# pcan-001.net
KiCad netlist of a schematic drawn in EAGLE
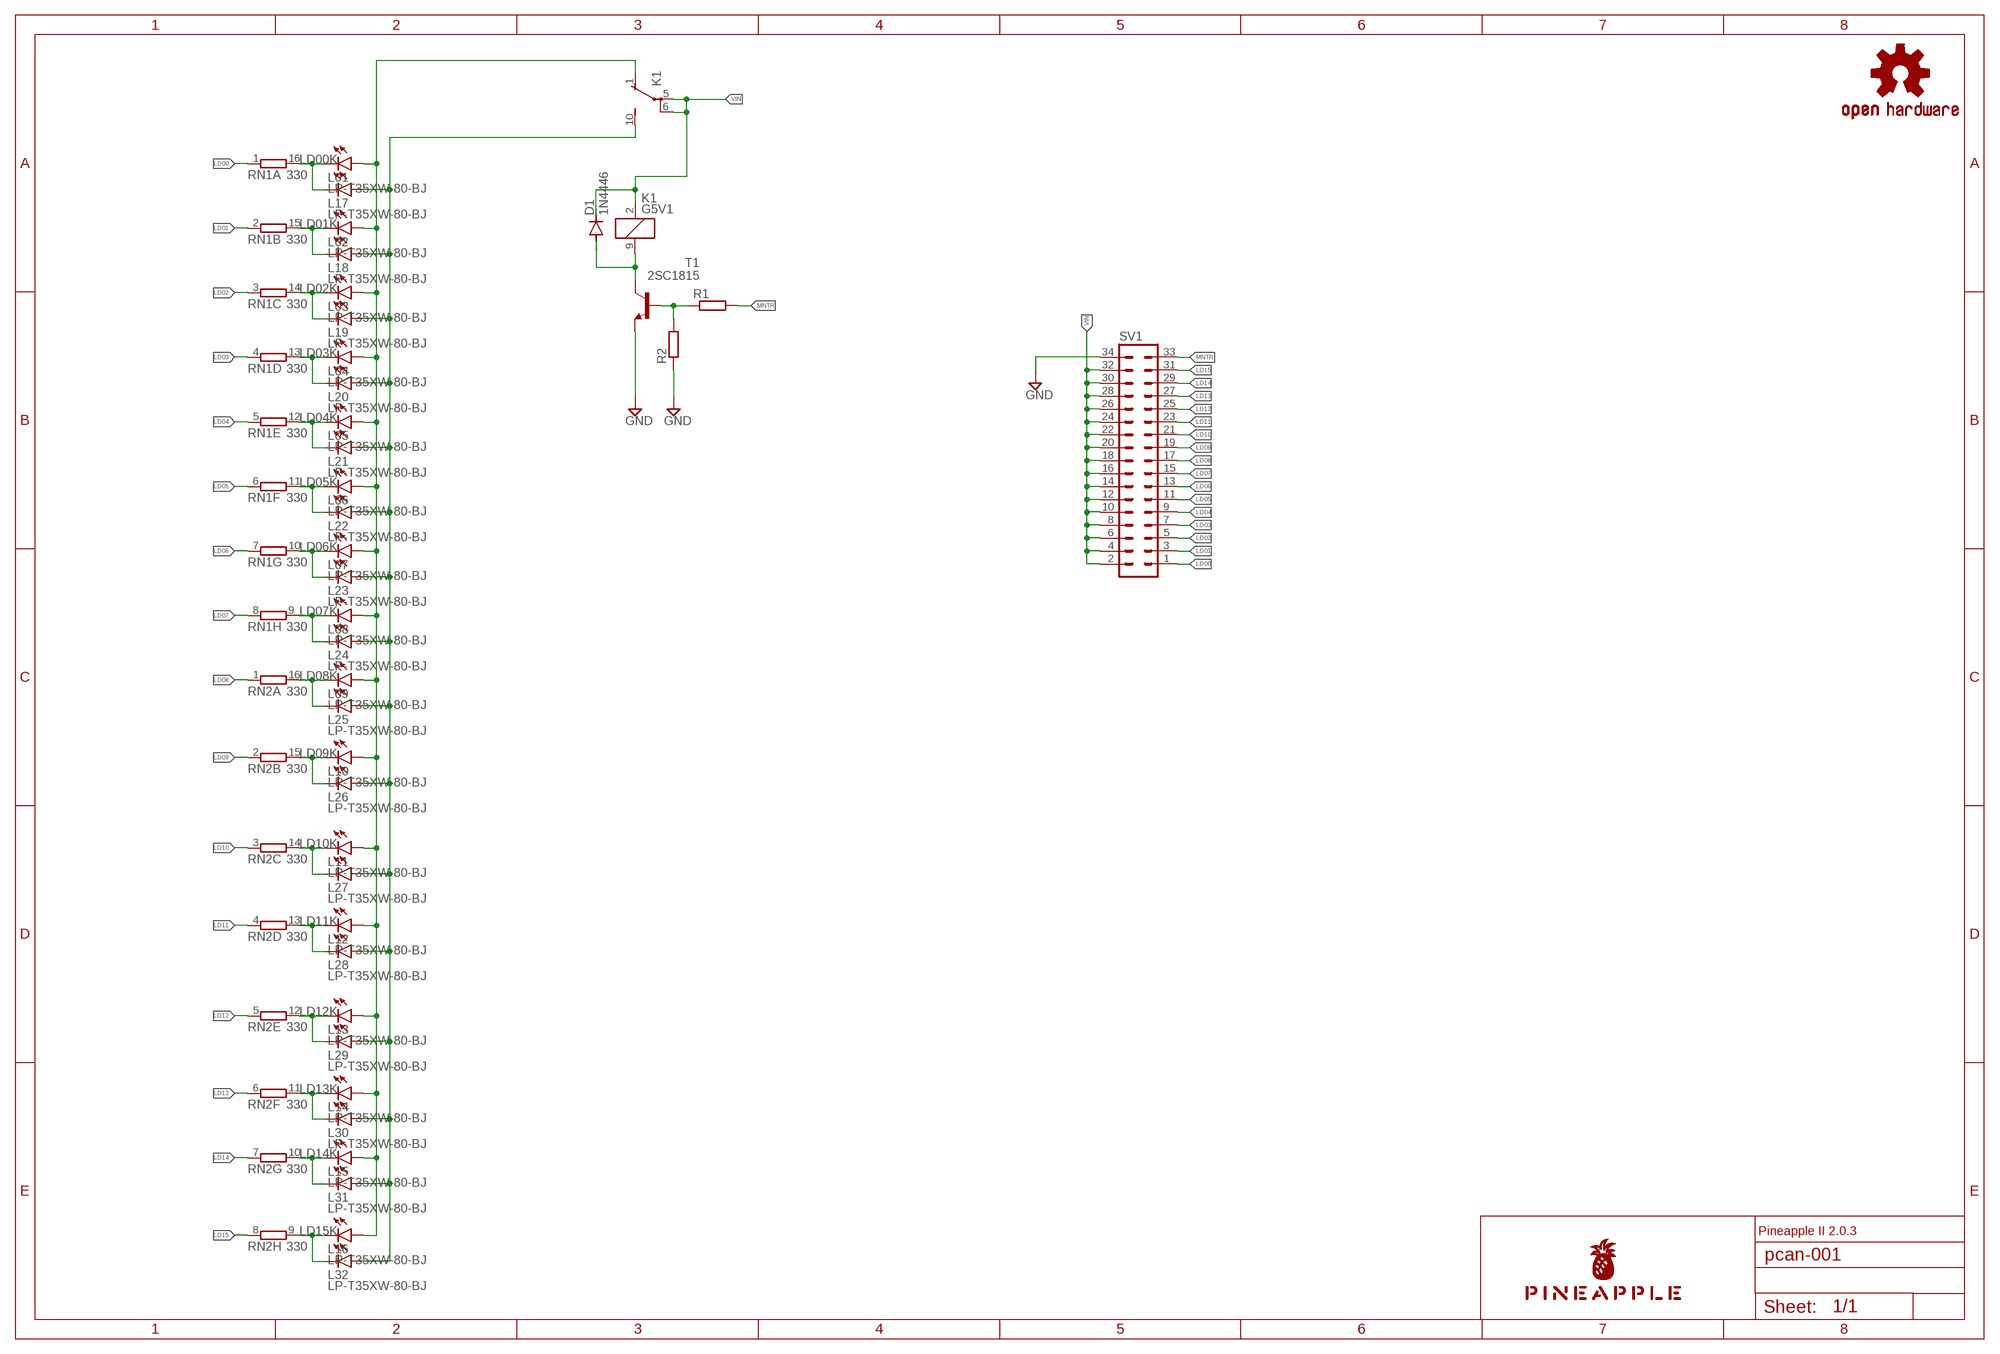
[diagram p0: schematic, sheet 1]

(export (version "E")
  (design (tool "Eeschema 10.0.6"))
  (components
    (comp (ref "D1")
      (value "1N4446")
      (footprint "eagle-import:DO35-10")
      (libsource (lib "eagle-import") (part "1N4446"))
    )
    (comp (ref "K1")
      (value "G5V1")
      (footprint "eagle-import:G5V1")
      (fields (field (name "MPN") "G5V-1-DC24"))
      (libsource (lib "eagle-import") (part "G5V1"))
    )
    (comp (ref "L01")
      (value "LP-T35XW-80-BJ")
      (footprint "eagle-import:KA-3528ASYC")
      (libsource (lib "eagle-import") (part "LEDKA-3528ASYC"))
    )
    (comp (ref "L02")
      (value "LP-T35XW-80-BJ")
      (footprint "eagle-import:KA-3528ASYC")
      (libsource (lib "eagle-import") (part "LEDKA-3528ASYC"))
    )
    (comp (ref "L03")
      (value "LP-T35XW-80-BJ")
      (footprint "eagle-import:KA-3528ASYC")
      (libsource (lib "eagle-import") (part "LEDKA-3528ASYC"))
    )
    (comp (ref "L04")
      (value "LP-T35XW-80-BJ")
      (footprint "eagle-import:KA-3528ASYC")
      (libsource (lib "eagle-import") (part "LEDKA-3528ASYC"))
    )
    (comp (ref "L05")
      (value "LP-T35XW-80-BJ")
      (footprint "eagle-import:KA-3528ASYC")
      (libsource (lib "eagle-import") (part "LEDKA-3528ASYC"))
    )
    (comp (ref "L06")
      (value "LP-T35XW-80-BJ")
      (footprint "eagle-import:KA-3528ASYC")
      (libsource (lib "eagle-import") (part "LEDKA-3528ASYC"))
    )
    (comp (ref "L07")
      (value "LP-T35XW-80-BJ")
      (footprint "eagle-import:KA-3528ASYC")
      (libsource (lib "eagle-import") (part "LEDKA-3528ASYC"))
    )
    (comp (ref "L08")
      (value "LP-T35XW-80-BJ")
      (footprint "eagle-import:KA-3528ASYC")
      (libsource (lib "eagle-import") (part "LEDKA-3528ASYC"))
    )
    (comp (ref "L09")
      (value "LP-T35XW-80-BJ")
      (footprint "eagle-import:KA-3528ASYC")
      (libsource (lib "eagle-import") (part "LEDKA-3528ASYC"))
    )
    (comp (ref "L10")
      (value "LP-T35XW-80-BJ")
      (footprint "eagle-import:KA-3528ASYC")
      (libsource (lib "eagle-import") (part "LEDKA-3528ASYC"))
    )
    (comp (ref "L11")
      (value "LP-T35XW-80-BJ")
      (footprint "eagle-import:KA-3528ASYC")
      (libsource (lib "eagle-import") (part "LEDKA-3528ASYC"))
    )
    (comp (ref "L12")
      (value "LP-T35XW-80-BJ")
      (footprint "eagle-import:KA-3528ASYC")
      (libsource (lib "eagle-import") (part "LEDKA-3528ASYC"))
    )
    (comp (ref "L13")
      (value "LP-T35XW-80-BJ")
      (footprint "eagle-import:KA-3528ASYC")
      (libsource (lib "eagle-import") (part "LEDKA-3528ASYC"))
    )
    (comp (ref "L14")
      (value "LP-T35XW-80-BJ")
      (footprint "eagle-import:KA-3528ASYC")
      (libsource (lib "eagle-import") (part "LEDKA-3528ASYC"))
    )
    (comp (ref "L15")
      (value "LP-T35XW-80-BJ")
      (footprint "eagle-import:KA-3528ASYC")
      (libsource (lib "eagle-import") (part "LEDKA-3528ASYC"))
    )
    (comp (ref "L16")
      (value "LP-T35XW-80-BJ")
      (footprint "eagle-import:KA-3528ASYC")
      (libsource (lib "eagle-import") (part "LEDKA-3528ASYC"))
    )
    (comp (ref "L17")
      (value "LP-T35XW-80-BJ")
      (footprint "eagle-import:KA-3528ASYC")
      (libsource (lib "eagle-import") (part "LEDKA-3528ASYC"))
    )
    (comp (ref "L18")
      (value "LP-T35XW-80-BJ")
      (footprint "eagle-import:KA-3528ASYC")
      (libsource (lib "eagle-import") (part "LEDKA-3528ASYC"))
    )
    (comp (ref "L19")
      (value "LP-T35XW-80-BJ")
      (footprint "eagle-import:KA-3528ASYC")
      (libsource (lib "eagle-import") (part "LEDKA-3528ASYC"))
    )
    (comp (ref "L20")
      (value "LP-T35XW-80-BJ")
      (footprint "eagle-import:KA-3528ASYC")
      (libsource (lib "eagle-import") (part "LEDKA-3528ASYC"))
    )
    (comp (ref "L21")
      (value "LP-T35XW-80-BJ")
      (footprint "eagle-import:KA-3528ASYC")
      (libsource (lib "eagle-import") (part "LEDKA-3528ASYC"))
    )
    (comp (ref "L22")
      (value "LP-T35XW-80-BJ")
      (footprint "eagle-import:KA-3528ASYC")
      (libsource (lib "eagle-import") (part "LEDKA-3528ASYC"))
    )
    (comp (ref "L23")
      (value "LP-T35XW-80-BJ")
      (footprint "eagle-import:KA-3528ASYC")
      (libsource (lib "eagle-import") (part "LEDKA-3528ASYC"))
    )
    (comp (ref "L24")
      (value "LP-T35XW-80-BJ")
      (footprint "eagle-import:KA-3528ASYC")
      (libsource (lib "eagle-import") (part "LEDKA-3528ASYC"))
    )
    (comp (ref "L25")
      (value "LP-T35XW-80-BJ")
      (footprint "eagle-import:KA-3528ASYC")
      (libsource (lib "eagle-import") (part "LEDKA-3528ASYC"))
    )
    (comp (ref "L26")
      (value "LP-T35XW-80-BJ")
      (footprint "eagle-import:KA-3528ASYC")
      (libsource (lib "eagle-import") (part "LEDKA-3528ASYC"))
    )
    (comp (ref "L27")
      (value "LP-T35XW-80-BJ")
      (footprint "eagle-import:KA-3528ASYC")
      (libsource (lib "eagle-import") (part "LEDKA-3528ASYC"))
    )
    (comp (ref "L28")
      (value "LP-T35XW-80-BJ")
      (footprint "eagle-import:KA-3528ASYC")
      (libsource (lib "eagle-import") (part "LEDKA-3528ASYC"))
    )
    (comp (ref "L29")
      (value "LP-T35XW-80-BJ")
      (footprint "eagle-import:KA-3528ASYC")
      (libsource (lib "eagle-import") (part "LEDKA-3528ASYC"))
    )
    (comp (ref "L30")
      (value "LP-T35XW-80-BJ")
      (footprint "eagle-import:KA-3528ASYC")
      (libsource (lib "eagle-import") (part "LEDKA-3528ASYC"))
    )
    (comp (ref "L31")
      (value "LP-T35XW-80-BJ")
      (footprint "eagle-import:KA-3528ASYC")
      (libsource (lib "eagle-import") (part "LEDKA-3528ASYC"))
    )
    (comp (ref "L32")
      (value "LP-T35XW-80-BJ")
      (footprint "eagle-import:KA-3528ASYC")
      (libsource (lib "eagle-import") (part "LEDKA-3528ASYC"))
    )
    (comp (ref "LOGO1")
      (value "OSHW-LOGOS-COPPER")
      (footprint "eagle-import:OSHW-LOGO-S_COPPER")
      (libsource (lib "eagle-import") (part "OSHW-LOGOS-COPPER"))
    )
    (comp (ref "R1")
      (value "R-EU_0204/5")
      (footprint "eagle-import:0204_5")
      (libsource (lib "eagle-import") (part "R-EU_0204/5"))
    )
    (comp (ref "R2")
      (value "R-EU_0204/5")
      (footprint "eagle-import:0204_5")
      (libsource (lib "eagle-import") (part "R-EU_0204/5"))
    )
    (comp (ref "RN1")
      (value "330")
      (footprint "eagle-import:DIL16")
      (libsource (lib "eagle-import") (part "8R-N"))
    )
    (comp (ref "RN2")
      (value "330")
      (footprint "eagle-import:DIL16")
      (libsource (lib "eagle-import") (part "8R-N"))
    )
    (comp (ref "SV1")
      (value "ML34L")
      (footprint "eagle-import:ML34L")
      (libsource (lib "eagle-import") (part "ML34L"))
    )
    (comp (ref "T1")
      (value "2SC1815")
      (footprint "eagle-import:TO92-ECB")
      (libsource (lib "eagle-import") (part "2SC1815"))
    )
    (comp (ref "U$1")
      (value "PINEAPPLE450_SILK")
      (footprint "eagle-import:PINEAPPLE450_SILK")
      (libsource (lib "eagle-import") (part "PINEAPPLE450_SILK"))
    )
  )
  (nets
    (net (code "1") (name "/LD00K") (class "Default")
      (node (ref "L01") (pin "C") (pinfunction "C_C") (pintype "passive"))
      (node (ref "L17") (pin "C") (pinfunction "C_C") (pintype "passive"))
      (node (ref "RN1") (pin "16") (pinfunction "2_16") (pintype "passive"))
    )
    (net (code "2") (name "/LD01K") (class "Default")
      (node (ref "L02") (pin "C") (pinfunction "C_C") (pintype "passive"))
      (node (ref "L18") (pin "C") (pinfunction "C_C") (pintype "passive"))
      (node (ref "RN1") (pin "15") (pinfunction "2_15") (pintype "passive"))
    )
    (net (code "3") (name "/LD02K") (class "Default")
      (node (ref "L03") (pin "C") (pinfunction "C_C") (pintype "passive"))
      (node (ref "L19") (pin "C") (pinfunction "C_C") (pintype "passive"))
      (node (ref "RN1") (pin "14") (pinfunction "2_14") (pintype "passive"))
    )
    (net (code "4") (name "/LD03K") (class "Default")
      (node (ref "L04") (pin "C") (pinfunction "C_C") (pintype "passive"))
      (node (ref "L20") (pin "C") (pinfunction "C_C") (pintype "passive"))
      (node (ref "RN1") (pin "13") (pinfunction "2_13") (pintype "passive"))
    )
    (net (code "5") (name "/LD04K") (class "Default")
      (node (ref "L05") (pin "C") (pinfunction "C_C") (pintype "passive"))
      (node (ref "L21") (pin "C") (pinfunction "C_C") (pintype "passive"))
      (node (ref "RN1") (pin "12") (pinfunction "2_12") (pintype "passive"))
    )
    (net (code "6") (name "/LD05K") (class "Default")
      (node (ref "L06") (pin "C") (pinfunction "C_C") (pintype "passive"))
      (node (ref "L22") (pin "C") (pinfunction "C_C") (pintype "passive"))
      (node (ref "RN1") (pin "11") (pinfunction "2_11") (pintype "passive"))
    )
    (net (code "7") (name "/LD06K") (class "Default")
      (node (ref "L07") (pin "C") (pinfunction "C_C") (pintype "passive"))
      (node (ref "L23") (pin "C") (pinfunction "C_C") (pintype "passive"))
      (node (ref "RN1") (pin "10") (pinfunction "2_10") (pintype "passive"))
    )
    (net (code "8") (name "/LD07K") (class "Default")
      (node (ref "L08") (pin "C") (pinfunction "C_C") (pintype "passive"))
      (node (ref "L24") (pin "C") (pinfunction "C_C") (pintype "passive"))
      (node (ref "RN1") (pin "9") (pinfunction "2_9") (pintype "passive"))
    )
    (net (code "9") (name "/LD08K") (class "Default")
      (node (ref "L09") (pin "C") (pinfunction "C_C") (pintype "passive"))
      (node (ref "L25") (pin "C") (pinfunction "C_C") (pintype "passive"))
      (node (ref "RN2") (pin "16") (pinfunction "2_16") (pintype "passive"))
    )
    (net (code "10") (name "/LD09K") (class "Default")
      (node (ref "L10") (pin "C") (pinfunction "C_C") (pintype "passive"))
      (node (ref "L26") (pin "C") (pinfunction "C_C") (pintype "passive"))
      (node (ref "RN2") (pin "15") (pinfunction "2_15") (pintype "passive"))
    )
    (net (code "11") (name "/LD10K") (class "Default")
      (node (ref "L11") (pin "C") (pinfunction "C_C") (pintype "passive"))
      (node (ref "L27") (pin "C") (pinfunction "C_C") (pintype "passive"))
      (node (ref "RN2") (pin "14") (pinfunction "2_14") (pintype "passive"))
    )
    (net (code "12") (name "/LD11K") (class "Default")
      (node (ref "L12") (pin "C") (pinfunction "C_C") (pintype "passive"))
      (node (ref "L28") (pin "C") (pinfunction "C_C") (pintype "passive"))
      (node (ref "RN2") (pin "13") (pinfunction "2_13") (pintype "passive"))
    )
    (net (code "13") (name "/LD12K") (class "Default")
      (node (ref "L13") (pin "C") (pinfunction "C_C") (pintype "passive"))
      (node (ref "L29") (pin "C") (pinfunction "C_C") (pintype "passive"))
      (node (ref "RN2") (pin "12") (pinfunction "2_12") (pintype "passive"))
    )
    (net (code "14") (name "/LD13K") (class "Default")
      (node (ref "L14") (pin "C") (pinfunction "C_C") (pintype "passive"))
      (node (ref "L30") (pin "C") (pinfunction "C_C") (pintype "passive"))
      (node (ref "RN2") (pin "11") (pinfunction "2_11") (pintype "passive"))
    )
    (net (code "15") (name "/LD14K") (class "Default")
      (node (ref "L15") (pin "C") (pinfunction "C_C") (pintype "passive"))
      (node (ref "L31") (pin "C") (pinfunction "C_C") (pintype "passive"))
      (node (ref "RN2") (pin "10") (pinfunction "2_10") (pintype "passive"))
    )
    (net (code "16") (name "/LD15K") (class "Default")
      (node (ref "L16") (pin "C") (pinfunction "C_C") (pintype "passive"))
      (node (ref "L32") (pin "C") (pinfunction "C_C") (pintype "passive"))
      (node (ref "RN2") (pin "9") (pinfunction "2_9") (pintype "passive"))
    )
    (net (code "17") (name "GND") (class "Default")
      (node (ref "R2") (pin "1") (pinfunction "1_1") (pintype "passive"))
      (node (ref "SV1") (pin "34") (pinfunction "34_34") (pintype "passive"))
      (node (ref "T1") (pin "E") (pinfunction "E_E") (pintype "passive"))
    )
    (net (code "18") (name "LD00") (class "Default")
      (node (ref "RN1") (pin "1") (pinfunction "1_1") (pintype "passive"))
      (node (ref "SV1") (pin "1") (pinfunction "1_1") (pintype "passive"))
    )
    (net (code "19") (name "LD01") (class "Default")
      (node (ref "RN1") (pin "2") (pinfunction "1_2") (pintype "passive"))
      (node (ref "SV1") (pin "3") (pinfunction "3_3") (pintype "passive"))
    )
    (net (code "20") (name "LD02") (class "Default")
      (node (ref "RN1") (pin "3") (pinfunction "1_3") (pintype "passive"))
      (node (ref "SV1") (pin "5") (pinfunction "5_5") (pintype "passive"))
    )
    (net (code "21") (name "LD03") (class "Default")
      (node (ref "RN1") (pin "4") (pinfunction "1_4") (pintype "passive"))
      (node (ref "SV1") (pin "7") (pinfunction "7_7") (pintype "passive"))
    )
    (net (code "22") (name "LD04") (class "Default")
      (node (ref "RN1") (pin "5") (pinfunction "1_5") (pintype "passive"))
      (node (ref "SV1") (pin "9") (pinfunction "9_9") (pintype "passive"))
    )
    (net (code "23") (name "LD05") (class "Default")
      (node (ref "RN1") (pin "6") (pinfunction "1_6") (pintype "passive"))
      (node (ref "SV1") (pin "11") (pinfunction "11_11") (pintype "passive"))
    )
    (net (code "24") (name "LD06") (class "Default")
      (node (ref "RN1") (pin "7") (pinfunction "1_7") (pintype "passive"))
      (node (ref "SV1") (pin "13") (pinfunction "13_13") (pintype "passive"))
    )
    (net (code "25") (name "LD07") (class "Default")
      (node (ref "RN1") (pin "8") (pinfunction "1_8") (pintype "passive"))
      (node (ref "SV1") (pin "15") (pinfunction "15_15") (pintype "passive"))
    )
    (net (code "26") (name "LD08") (class "Default")
      (node (ref "RN2") (pin "1") (pinfunction "1_1") (pintype "passive"))
      (node (ref "SV1") (pin "17") (pinfunction "17_17") (pintype "passive"))
    )
    (net (code "27") (name "LD09") (class "Default")
      (node (ref "RN2") (pin "2") (pinfunction "1_2") (pintype "passive"))
      (node (ref "SV1") (pin "19") (pinfunction "19_19") (pintype "passive"))
    )
    (net (code "28") (name "LD10") (class "Default")
      (node (ref "RN2") (pin "3") (pinfunction "1_3") (pintype "passive"))
      (node (ref "SV1") (pin "21") (pinfunction "21_21") (pintype "passive"))
    )
    (net (code "29") (name "LD11") (class "Default")
      (node (ref "RN2") (pin "4") (pinfunction "1_4") (pintype "passive"))
      (node (ref "SV1") (pin "23") (pinfunction "23_23") (pintype "passive"))
    )
    (net (code "30") (name "LD12") (class "Default")
      (node (ref "RN2") (pin "5") (pinfunction "1_5") (pintype "passive"))
      (node (ref "SV1") (pin "25") (pinfunction "25_25") (pintype "passive"))
    )
    (net (code "31") (name "LD13") (class "Default")
      (node (ref "RN2") (pin "6") (pinfunction "1_6") (pintype "passive"))
      (node (ref "SV1") (pin "27") (pinfunction "27_27") (pintype "passive"))
    )
    (net (code "32") (name "LD14") (class "Default")
      (node (ref "RN2") (pin "7") (pinfunction "1_7") (pintype "passive"))
      (node (ref "SV1") (pin "29") (pinfunction "29_29") (pintype "passive"))
    )
    (net (code "33") (name "LD15") (class "Default")
      (node (ref "RN2") (pin "8") (pinfunction "1_8") (pintype "passive"))
      (node (ref "SV1") (pin "31") (pinfunction "31_31") (pintype "passive"))
    )
    (net (code "34") (name "MNTR") (class "Default")
      (node (ref "R1") (pin "2") (pinfunction "2_2") (pintype "passive"))
      (node (ref "SV1") (pin "33") (pinfunction "33_33") (pintype "passive"))
    )
    (net (code "35") (name "Net-(K1A-2)") (class "Default")
      (node (ref "D1") (pin "A") (pinfunction "A_A") (pintype "passive"))
      (node (ref "K1") (pin "9") (pinfunction "2_9") (pintype "passive"))
      (node (ref "T1") (pin "C") (pinfunction "C_C") (pintype "passive"))
    )
    (net (code "36") (name "Net-(K1B-O)") (class "Default")
      (node (ref "K1") (pin "1") (pinfunction "O_1") (pintype "passive"))
      (node (ref "L01") (pin "A") (pinfunction "A_A") (pintype "passive"))
      (node (ref "L02") (pin "A") (pinfunction "A_A") (pintype "passive"))
      (node (ref "L03") (pin "A") (pinfunction "A_A") (pintype "passive"))
      (node (ref "L04") (pin "A") (pinfunction "A_A") (pintype "passive"))
      (node (ref "L05") (pin "A") (pinfunction "A_A") (pintype "passive"))
      (node (ref "L06") (pin "A") (pinfunction "A_A") (pintype "passive"))
      (node (ref "L07") (pin "A") (pinfunction "A_A") (pintype "passive"))
      (node (ref "L08") (pin "A") (pinfunction "A_A") (pintype "passive"))
      (node (ref "L09") (pin "A") (pinfunction "A_A") (pintype "passive"))
      (node (ref "L10") (pin "A") (pinfunction "A_A") (pintype "passive"))
      (node (ref "L11") (pin "A") (pinfunction "A_A") (pintype "passive"))
      (node (ref "L12") (pin "A") (pinfunction "A_A") (pintype "passive"))
      (node (ref "L13") (pin "A") (pinfunction "A_A") (pintype "passive"))
      (node (ref "L14") (pin "A") (pinfunction "A_A") (pintype "passive"))
      (node (ref "L15") (pin "A") (pinfunction "A_A") (pintype "passive"))
      (node (ref "L16") (pin "A") (pinfunction "A_A") (pintype "passive"))
    )
    (net (code "37") (name "Net-(K1B-S)") (class "Default")
      (node (ref "K1") (pin "10") (pinfunction "S_10") (pintype "passive"))
      (node (ref "L17") (pin "A") (pinfunction "A_A") (pintype "passive"))
      (node (ref "L18") (pin "A") (pinfunction "A_A") (pintype "passive"))
      (node (ref "L19") (pin "A") (pinfunction "A_A") (pintype "passive"))
      (node (ref "L20") (pin "A") (pinfunction "A_A") (pintype "passive"))
      (node (ref "L21") (pin "A") (pinfunction "A_A") (pintype "passive"))
      (node (ref "L22") (pin "A") (pinfunction "A_A") (pintype "passive"))
      (node (ref "L23") (pin "A") (pinfunction "A_A") (pintype "passive"))
      (node (ref "L24") (pin "A") (pinfunction "A_A") (pintype "passive"))
      (node (ref "L25") (pin "A") (pinfunction "A_A") (pintype "passive"))
      (node (ref "L26") (pin "A") (pinfunction "A_A") (pintype "passive"))
      (node (ref "L27") (pin "A") (pinfunction "A_A") (pintype "passive"))
      (node (ref "L28") (pin "A") (pinfunction "A_A") (pintype "passive"))
      (node (ref "L29") (pin "A") (pinfunction "A_A") (pintype "passive"))
      (node (ref "L30") (pin "A") (pinfunction "A_A") (pintype "passive"))
      (node (ref "L31") (pin "A") (pinfunction "A_A") (pintype "passive"))
      (node (ref "L32") (pin "A") (pinfunction "A_A") (pintype "passive"))
    )
    (net (code "38") (name "Net-(R1-Pad1)") (class "Default")
      (node (ref "R1") (pin "1") (pinfunction "1_1") (pintype "passive"))
      (node (ref "R2") (pin "2") (pinfunction "2_2") (pintype "passive"))
      (node (ref "T1") (pin "B") (pinfunction "B_B") (pintype "passive"))
    )
    (net (code "39") (name "VIN") (class "Default")
      (node (ref "D1") (pin "C") (pinfunction "C_C") (pintype "passive"))
      (node (ref "K1") (pin "2") (pinfunction "1_2") (pintype "passive"))
      (node (ref "K1") (pin "5") (pinfunction "P_5") (pintype "passive"))
      (node (ref "K1") (pin "6") (pinfunction "P_6") (pintype "passive"))
      (node (ref "SV1") (pin "10") (pinfunction "10_10") (pintype "passive"))
      (node (ref "SV1") (pin "12") (pinfunction "12_12") (pintype "passive"))
      (node (ref "SV1") (pin "14") (pinfunction "14_14") (pintype "passive"))
      (node (ref "SV1") (pin "16") (pinfunction "16_16") (pintype "passive"))
      (node (ref "SV1") (pin "18") (pinfunction "18_18") (pintype "passive"))
      (node (ref "SV1") (pin "2") (pinfunction "2_2") (pintype "passive"))
      (node (ref "SV1") (pin "20") (pinfunction "20_20") (pintype "passive"))
      (node (ref "SV1") (pin "22") (pinfunction "22_22") (pintype "passive"))
      (node (ref "SV1") (pin "24") (pinfunction "24_24") (pintype "passive"))
      (node (ref "SV1") (pin "26") (pinfunction "26_26") (pintype "passive"))
      (node (ref "SV1") (pin "28") (pinfunction "28_28") (pintype "passive"))
      (node (ref "SV1") (pin "30") (pinfunction "30_30") (pintype "passive"))
      (node (ref "SV1") (pin "32") (pinfunction "32_32") (pintype "passive"))
      (node (ref "SV1") (pin "4") (pinfunction "4_4") (pintype "passive"))
      (node (ref "SV1") (pin "6") (pinfunction "6_6") (pintype "passive"))
      (node (ref "SV1") (pin "8") (pinfunction "8_8") (pintype "passive"))
    )
  )
)
